# Memoria_I2C.net
KiCad netlist of a schematic drawn in Altium Designer
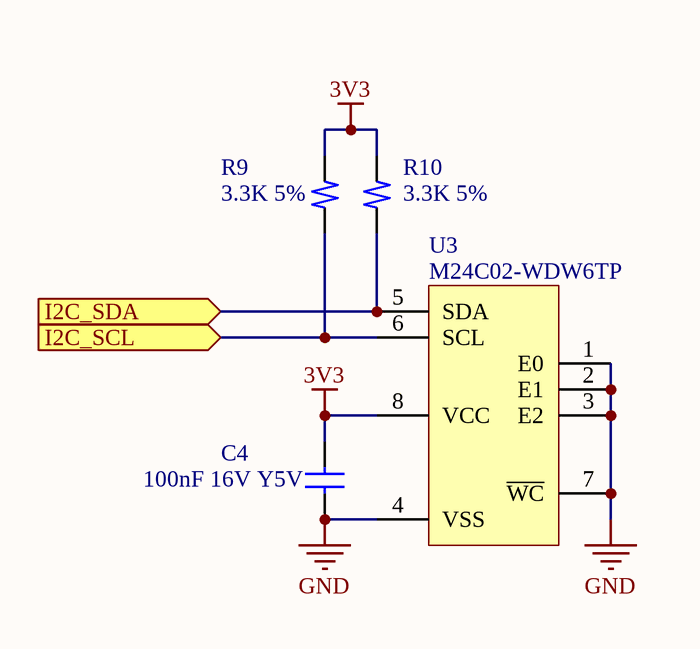
[diagram p0: Memoria_I2C.SchDoc]

(export (version "E")
  (design (tool "Eeschema 10.0.6"))
  (components
    (comp (ref "C4")
      (value "100nF 16V Y5V")
      (footprint "C_0402")
      (description "Ceramic Capacitor SMD 0402")
      (libsource (lib "Oxy_Lib") (part "Ceramic Capacitor"))
    )
    (comp (ref "R9")
      (value "3.3K 5%")
      (footprint "R_0402")
      (description "Resistor SMD 0402")
      (libsource (lib "Oxy_Lib") (part "Resistor"))
    )
    (comp (ref "R10")
      (value "3.3K 5%")
      (footprint "R_0402")
      (description "Resistor SMD 0402")
      (libsource (lib "Oxy_Lib") (part "Resistor"))
    )
    (comp (ref "U3")
      (value "M24C02-WDW6TP")
      (footprint "TSSOP-8")
      (description "M24C02-WDW6TP 2.5-5V 2Kbit Serial I2C Bus EEPROM")
      (libsource (lib "Oxy_Lib") (part "EEPROM M24C02-WDW6TP"))
    )
  )
  (nets
    (net (code "1") (name "/I2C_SCL") (class "Default")
      (node (ref "R9") (pin "1") (pinfunction "1_1") (pintype "passive"))
      (node (ref "U3") (pin "6") (pinfunction "SCL_6") (pintype "passive"))
    )
    (net (code "2") (name "/I2C_SDA") (class "Default")
      (node (ref "R10") (pin "1") (pinfunction "1_1") (pintype "passive"))
      (node (ref "U3") (pin "5") (pinfunction "SDA_5") (pintype "passive"))
    )
    (net (code "3") (name "3V3") (class "Default")
      (node (ref "C4") (pin "1") (pinfunction "1_1") (pintype "passive"))
      (node (ref "R10") (pin "2") (pinfunction "2_2") (pintype "passive"))
      (node (ref "R9") (pin "2") (pinfunction "2_2") (pintype "passive"))
      (node (ref "U3") (pin "8") (pinfunction "VCC_8") (pintype "passive"))
    )
    (net (code "4") (name "GND") (class "Default")
      (node (ref "C4") (pin "2") (pinfunction "2_2") (pintype "passive"))
      (node (ref "U3") (pin "1") (pinfunction "E0_1") (pintype "passive"))
      (node (ref "U3") (pin "2") (pinfunction "E1_2") (pintype "passive"))
      (node (ref "U3") (pin "3") (pinfunction "E2_3") (pintype "passive"))
      (node (ref "U3") (pin "4") (pinfunction "VSS_4") (pintype "passive"))
      (node (ref "U3") (pin "7") (pinfunction "~{WC}_7") (pintype "passive"))
    )
  )
)
